# SparkFun_XBee_Arduino_Shield_Qwiic.net
KiCad netlist of a schematic drawn in EAGLE
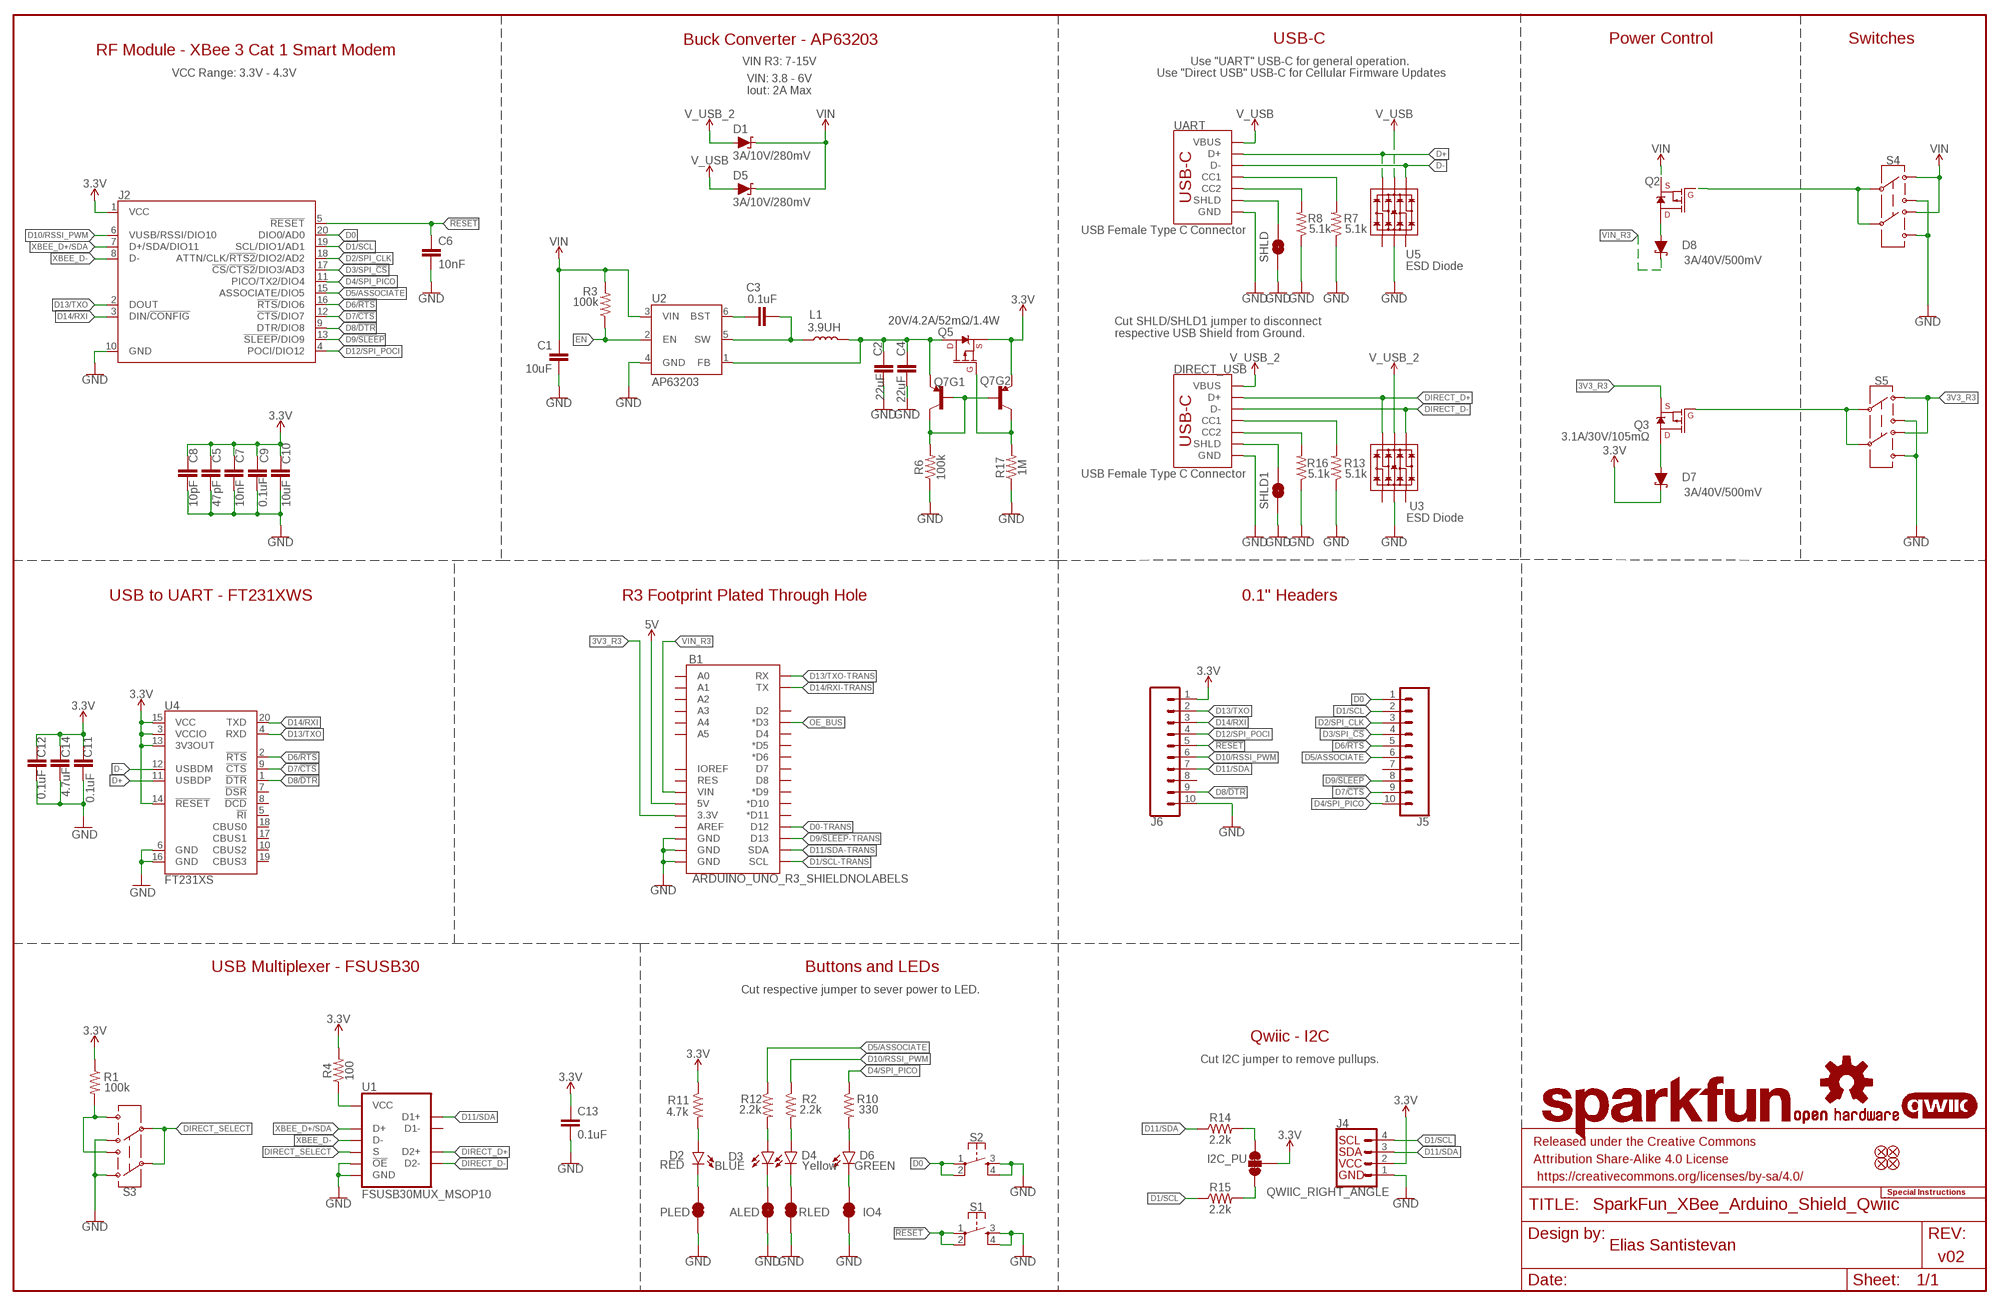
[diagram p0: schematic, sheet 1]

(export (version "E")
  (design (tool "Eeschema 10.0.6"))
  (components
    (comp (ref "ALED")
      (value "JUMPER-SMT_2_NC_TRACE_SILK")
      (footprint "eagle-import:SMT-JUMPER_2_NC_TRACE_SILK")
      (libsource (lib "eagle-import") (part "JUMPER-SMT_2_NC_TRACE_SILK"))
    )
    (comp (ref "B1")
      (value "ARDUINO_UNO_R3_SHIELDNOLABELS")
      (footprint "eagle-import:UNO_R3_SHIELD_NOLABELS")
      (libsource (lib "eagle-import") (part "ARDUINO_UNO_R3_SHIELDNOLABELS"))
    )
    (comp (ref "C1")
      (value "10uF")
      (footprint "eagle-import:1210")
      (libsource (lib "eagle-import") (part "10UF-1210-50V-20%"))
    )
    (comp (ref "C2")
      (value "22uF")
      (footprint "eagle-import:0603")
      (libsource (lib "eagle-import") (part "22UF-0603-6.3V-20%"))
    )
    (comp (ref "C3")
      (value "0.1uF")
      (footprint "eagle-import:0603")
      (libsource (lib "eagle-import") (part "0.1UF-0603-25V-5%"))
    )
    (comp (ref "C4")
      (value "22uF")
      (footprint "eagle-import:0603")
      (libsource (lib "eagle-import") (part "22UF-0603-6.3V-20%"))
    )
    (comp (ref "C5")
      (value "47pF")
      (footprint "eagle-import:0603")
      (libsource (lib "eagle-import") (part "47PF-0603-50V-5%"))
    )
    (comp (ref "C6")
      (value "10nF")
      (footprint "eagle-import:0603")
      (libsource (lib "eagle-import") (part "10NF-0603-50V-10%"))
    )
    (comp (ref "C7")
      (value "10nF")
      (footprint "eagle-import:0603")
      (libsource (lib "eagle-import") (part "10NF-0603-50V-10%"))
    )
    (comp (ref "C8")
      (value "10pF")
      (footprint "eagle-import:0603")
      (libsource (lib "eagle-import") (part "10PF-0603-50V-5%"))
    )
    (comp (ref "C9")
      (value "0.1uF")
      (footprint "eagle-import:0603")
      (libsource (lib "eagle-import") (part "0.1UF-0603-25V-(+80/-20%)"))
    )
    (comp (ref "C10")
      (value "10uF")
      (footprint "eagle-import:0603")
      (libsource (lib "eagle-import") (part "10UF-0603-6.3V-20%"))
    )
    (comp (ref "C11")
      (value "0.1uF")
      (footprint "eagle-import:0603")
      (libsource (lib "eagle-import") (part "0.1UF-0603-25V-(+80/-20%)"))
    )
    (comp (ref "C12")
      (value "0.1uF")
      (footprint "eagle-import:0603")
      (libsource (lib "eagle-import") (part "0.1UF-0603-25V-(+80/-20%)"))
    )
    (comp (ref "C13")
      (value "0.1uF")
      (footprint "eagle-import:0603")
      (libsource (lib "eagle-import") (part "0.1UF-0603-25V-(+80/-20%)"))
    )
    (comp (ref "C14")
      (value "4.7uF")
      (footprint "eagle-import:0603")
      (libsource (lib "eagle-import") (part "4.7UF-0603-6.3V-(10%)"))
    )
    (comp (ref "D1")
      (value "3A/10V/280mV")
      (footprint "eagle-import:SOD-323")
      (libsource (lib "eagle-import") (part "DIODE-SCHOTTKY-BAT60A"))
    )
    (comp (ref "D2")
      (value "RED")
      (footprint "eagle-import:LED-0603")
      (libsource (lib "eagle-import") (part "LED-RED_0603-KB"))
    )
    (comp (ref "D3")
      (value "BLUE")
      (footprint "eagle-import:LED-0603")
      (libsource (lib "eagle-import") (part "LED-BLUE0603"))
    )
    (comp (ref "D4")
      (value "Yellow")
      (footprint "eagle-import:LED-0603")
      (libsource (lib "eagle-import") (part "LED-YELLOW0603"))
    )
    (comp (ref "D5")
      (value "3A/10V/280mV")
      (footprint "eagle-import:SOD-323")
      (libsource (lib "eagle-import") (part "DIODE-SCHOTTKY-BAT60A"))
    )
    (comp (ref "D6")
      (value "GREEN")
      (footprint "eagle-import:LED-0603")
      (libsource (lib "eagle-import") (part "LED-GREEN0603"))
    )
    (comp (ref "D7")
      (value "3A/40V/500mV")
      (footprint "eagle-import:SMA-DIODE")
      (libsource (lib "eagle-import") (part "DIODE-SCHOTTKY-B340A"))
    )
    (comp (ref "D8")
      (value "3A/40V/500mV")
      (footprint "eagle-import:SMA-DIODE")
      (libsource (lib "eagle-import") (part "DIODE-SCHOTTKY-B340A"))
    )
    (comp (ref "DIRECT_USB")
      (value "USB Female Type C Connector")
      (footprint "eagle-import:USB-C-16P-4LAYER-ISOLATED")
      (libsource (lib "eagle-import") (part "USB_C_4-LAYER-ISOLATED"))
    )
    (comp (ref "FD1")
      (value "FIDUCIAL1X2")
      (footprint "eagle-import:FIDUCIAL-1X2")
      (libsource (lib "eagle-import") (part "FIDUCIAL1X2"))
    )
    (comp (ref "FD2")
      (value "FIDUCIAL1X2")
      (footprint "eagle-import:FIDUCIAL-1X2")
      (libsource (lib "eagle-import") (part "FIDUCIAL1X2"))
    )
    (comp (ref "FD3")
      (value "FIDUCIAL1X2")
      (footprint "eagle-import:FIDUCIAL-1X2")
      (libsource (lib "eagle-import") (part "FIDUCIAL1X2"))
    )
    (comp (ref "FD4")
      (value "FIDUCIAL1X2")
      (footprint "eagle-import:FIDUCIAL-1X2")
      (libsource (lib "eagle-import") (part "FIDUCIAL1X2"))
    )
    (comp (ref "FRAME1")
      (value "FRAME-LEDGER")
      (footprint "eagle-import:CREATIVE_COMMONS")
      (libsource (lib "eagle-import") (part "FRAME-LEDGER"))
    )
    (comp (ref "I2C_PU")
      (value "JUMPER-SMT_3_2-NC_TRACE_SILK")
      (footprint "eagle-import:SMT-JUMPER_3_2-NC_TRACE_SILK")
      (libsource (lib "eagle-import") (part "JUMPER-SMT_3_2-NC_TRACE_SILK"))
    )
    (comp (ref "IO4")
      (value "JUMPER-SMT_2_NC_TRACE_SILK")
      (footprint "eagle-import:SMT-JUMPER_2_NC_TRACE_SILK")
      (libsource (lib "eagle-import") (part "JUMPER-SMT_2_NC_TRACE_SILK"))
    )
    (comp (ref "J2")
      (value "XBEE_UPDATEXBEE_SMD")
      (footprint "eagle-import:XBEE3-SMD")
      (libsource (lib "eagle-import") (part "XBEE_UPDATEXBEE_SMD"))
    )
    (comp (ref "J4")
      (value "QWIIC_RIGHT_ANGLE")
      (footprint "eagle-import:JST04_1MM_RA")
      (libsource (lib "eagle-import") (part "QWIIC_CONNECTORJS-1MM"))
    )
    (comp (ref "J5")
      (value "CONN_10NO_SILK_PTH_FEMALE")
      (footprint "eagle-import:1X10_NO_SILK")
      (libsource (lib "eagle-import") (part "CONN_10NO_SILK_PTH_FEMALE"))
    )
    (comp (ref "J6")
      (value "CONN_10NO_SILK_PTH_FEMALE")
      (footprint "eagle-import:1X10_NO_SILK")
      (libsource (lib "eagle-import") (part "CONN_10NO_SILK_PTH_FEMALE"))
    )
    (comp (ref "L1")
      (value "3.9UH")
      (footprint "eagle-import:INDUCTOR_3.9UH")
      (libsource (lib "eagle-import") (part "3.9UH"))
    )
    (comp (ref "LOGO1")
      (value "SFE_LOGO_NAMEBLANK")
      (footprint "eagle-import:BLANK")
      (libsource (lib "eagle-import") (part "SFE_LOGO_NAMEBLANK"))
    )
    (comp (ref "LOGO2")
      (value "OSHW-LOGOS")
      (footprint "eagle-import:OSHW-LOGO-S")
      (libsource (lib "eagle-import") (part "OSHW-LOGOS"))
    )
    (comp (ref "LOGO3")
      (value "QWIIC_LOGO_4MM")
      (footprint "eagle-import:QWIIC_4MM")
      (libsource (lib "eagle-import") (part "QWIIC_LOGO_4MM"))
    )
    (comp (ref "LOGO4")
      (value "SPECIAL_INSTRUCTIONS-ORDERING")
      (footprint "eagle-import:ORDERING_INSTRUCTIONS")
      (libsource (lib "eagle-import") (part "SPECIAL_INSTRUCTIONS-ORDERING"))
    )
    (comp (ref "PLED")
      (value "JUMPER-SMT_2_NC_TRACE_SILK")
      (footprint "eagle-import:SMT-JUMPER_2_NC_TRACE_SILK")
      (libsource (lib "eagle-import") (part "JUMPER-SMT_2_NC_TRACE_SILK"))
    )
    (comp (ref "Q2")
      (value "20V/4.2A/52mΩ/1.4W")
      (footprint "eagle-import:SOT23-3")
      (libsource (lib "eagle-import") (part "MOSFET_PCH-DMG2305UX-7"))
    )
    (comp (ref "Q3")
      (value "3.1A/30V/105mΩ")
      (footprint "eagle-import:SOT23-3")
      (libsource (lib "eagle-import") (part "MOSFET_PCH-DMG2307L"))
    )
    (comp (ref "Q5")
      (value "20V/4.2A/52mΩ/1.4W")
      (footprint "eagle-import:SOT23-3")
      (libsource (lib "eagle-import") (part "MOSFET_PCH-DMG2305UX-7"))
    )
    (comp (ref "Q7")
      (value "TRANS_PNP_DUALSOT-363")
      (footprint "eagle-import:SOT363_PHILIPS")
      (libsource (lib "eagle-import") (part "TRANS_PNP_DUALSOT-363"))
    )
    (comp (ref "R1")
      (value "100k")
      (footprint "eagle-import:0603")
      (libsource (lib "eagle-import") (part "100KOHM-0603-1/10W-1%"))
    )
    (comp (ref "R2")
      (value "2.2k")
      (footprint "eagle-import:0603")
      (libsource (lib "eagle-import") (part "2.2KOHM-0603-1/10W-1%"))
    )
    (comp (ref "R3")
      (value "100k")
      (footprint "eagle-import:0603")
      (libsource (lib "eagle-import") (part "100KOHM-0603-1/10W-1%"))
    )
    (comp (ref "R4")
      (value "100")
      (footprint "eagle-import:0603")
      (libsource (lib "eagle-import") (part "100OHM-0603-1/10W-1%"))
    )
    (comp (ref "R6")
      (value "100k")
      (footprint "eagle-import:0603")
      (libsource (lib "eagle-import") (part "100KOHM-0603-1/10W-1%"))
    )
    (comp (ref "R7")
      (value "5.1k")
      (footprint "eagle-import:0603")
      (libsource (lib "eagle-import") (part "5.1KOHM5.1KOHM-0603-1/10W-1%"))
    )
    (comp (ref "R8")
      (value "5.1k")
      (footprint "eagle-import:0603")
      (libsource (lib "eagle-import") (part "5.1KOHM5.1KOHM-0603-1/10W-1%"))
    )
    (comp (ref "R10")
      (value "330")
      (footprint "eagle-import:0603")
      (libsource (lib "eagle-import") (part "330OHM-0603-1/10W-1%"))
    )
    (comp (ref "R11")
      (value "4.7k")
      (footprint "eagle-import:0603")
      (libsource (lib "eagle-import") (part "4.7KOHM-0603-1/10W-1%"))
    )
    (comp (ref "R12")
      (value "2.2k")
      (footprint "eagle-import:0603")
      (libsource (lib "eagle-import") (part "2.2KOHM-0603-1/10W-1%"))
    )
    (comp (ref "R13")
      (value "5.1k")
      (footprint "eagle-import:0603")
      (libsource (lib "eagle-import") (part "5.1KOHM5.1KOHM-0603-1/10W-1%"))
    )
    (comp (ref "R14")
      (value "2.2k")
      (footprint "eagle-import:0603")
      (libsource (lib "eagle-import") (part "2.2KOHM-0603-1/10W-1%"))
    )
    (comp (ref "R15")
      (value "2.2k")
      (footprint "eagle-import:0603")
      (libsource (lib "eagle-import") (part "2.2KOHM-0603-1/10W-1%"))
    )
    (comp (ref "R16")
      (value "5.1k")
      (footprint "eagle-import:0603")
      (libsource (lib "eagle-import") (part "5.1KOHM5.1KOHM-0603-1/10W-1%"))
    )
    (comp (ref "R17")
      (value "1M")
      (footprint "eagle-import:0603")
      (libsource (lib "eagle-import") (part "1MOHM-0603-1/4W-5%"))
    )
    (comp (ref "RLED")
      (value "JUMPER-SMT_2_NC_TRACE_SILK")
      (footprint "eagle-import:SMT-JUMPER_2_NC_TRACE_SILK")
      (libsource (lib "eagle-import") (part "JUMPER-SMT_2_NC_TRACE_SILK"))
    )
    (comp (ref "S1")
      (value "MOMENTARY-SWITCH-SPST-2-SMD-5.2MM-TALL")
      (footprint "eagle-import:TACTILE_SWITCH_SMD_5.2MM")
      (libsource (lib "eagle-import") (part "MOMENTARY-SWITCH-SPST-2-SMD-5.2MM-TALL"))
    )
    (comp (ref "S2")
      (value "MOMENTARY-SWITCH-SPST-2-SMD-5.2MM-TALL")
      (footprint "eagle-import:TACTILE_SWITCH_SMD_5.2MM")
      (libsource (lib "eagle-import") (part "MOMENTARY-SWITCH-SPST-2-SMD-5.2MM-TALL"))
    )
    (comp (ref "S3")
      (value "SWITCH-DPDT-SMD-AYZ0202")
      (footprint "eagle-import:SWITCH_DPDT_SMD_AYZ0202")
      (libsource (lib "eagle-import") (part "SWITCH-DPDT-SMD-AYZ0202"))
    )
    (comp (ref "S4")
      (value "SWITCH-DPDT-SMD-AYZ0202")
      (footprint "eagle-import:SWITCH_DPDT_SMD_AYZ0202")
      (libsource (lib "eagle-import") (part "SWITCH-DPDT-SMD-AYZ0202"))
    )
    (comp (ref "S5")
      (value "SWITCH-DPDT-SMD-AYZ0202")
      (footprint "eagle-import:SWITCH_DPDT_SMD_AYZ0202")
      (libsource (lib "eagle-import") (part "SWITCH-DPDT-SMD-AYZ0202"))
    )
    (comp (ref "SHLD")
      (value "JUMPER-SMT_2_NC_TRACE_SILK")
      (footprint "eagle-import:SMT-JUMPER_2_NC_TRACE_SILK")
      (libsource (lib "eagle-import") (part "JUMPER-SMT_2_NC_TRACE_SILK"))
    )
    (comp (ref "SHLD1")
      (value "JUMPER-SMT_2_NC_TRACE_SILK")
      (footprint "eagle-import:SMT-JUMPER_2_NC_TRACE_SILK")
      (libsource (lib "eagle-import") (part "JUMPER-SMT_2_NC_TRACE_SILK"))
    )
    (comp (ref "U1")
      (value "FSUSB30MUX_MSOP10")
      (footprint "eagle-import:MSOP10")
      (libsource (lib "eagle-import") (part "FSUSB30MUX_MSOP10"))
    )
    (comp (ref "U2")
      (value "AP63203")
      (footprint "eagle-import:SOT23-6")
      (libsource (lib "eagle-import") (part "AP63203"))
    )
    (comp (ref "U3")
      (value "ESD Diode")
      (footprint "eagle-import:SOT-23-6")
      (libsource (lib "eagle-import") (part "TVS_DIODE_ARRAY_DT1042-04SO-7"))
    )
    (comp (ref "U4")
      (value "FT231XS")
      (footprint "eagle-import:SSOP20_L")
      (libsource (lib "eagle-import") (part "FT231XS"))
    )
    (comp (ref "U5")
      (value "ESD Diode")
      (footprint "eagle-import:SOT-23-6")
      (libsource (lib "eagle-import") (part "TVS_DIODE_ARRAY_DT1042-04SO-7"))
    )
    (comp (ref "UART")
      (value "USB Female Type C Connector")
      (footprint "eagle-import:USB-C-16P-4LAYER-ISOLATED")
      (libsource (lib "eagle-import") (part "USB_C_4-LAYER-ISOLATED"))
    )
  )
  (nets
    (net (code "1") (name "/D3{slash}SPI_~{CS}") (class "Default")
      (node (ref "J2") (pin "17") (pinfunction "~{CS}/~{CTS2}/DIO3/AD3_17") (pintype "bidirectional"))
      (node (ref "J5") (pin "4") (pinfunction "4_4") (pintype "passive"))
    )
    (net (code "2") (name "/D6{slash}~{RTS}") (class "Default")
      (node (ref "J2") (pin "16") (pinfunction "~{RTS}/DIO6_16") (pintype "input"))
      (node (ref "J5") (pin "5") (pinfunction "5_5") (pintype "passive"))
      (node (ref "U4") (pin "2") (pinfunction "~{RTS}_2") (pintype "bidirectional"))
    )
    (net (code "3") (name "/D7{slash}~{CTS}") (class "Default")
      (node (ref "J2") (pin "12") (pinfunction "~{CTS}/DIO7_12") (pintype "output"))
      (node (ref "J5") (pin "9") (pinfunction "9_9") (pintype "passive"))
      (node (ref "U4") (pin "9") (pinfunction "~{CTS}_9") (pintype "bidirectional"))
    )
    (net (code "4") (name "/D8{slash}~{DTR}") (class "Default")
      (node (ref "J2") (pin "9") (pinfunction "DTR/DIO8_9") (pintype "bidirectional"))
      (node (ref "J6") (pin "9") (pinfunction "9_9") (pintype "passive"))
      (node (ref "U4") (pin "1") (pinfunction "~{DTR}_1") (pintype "bidirectional"))
    )
    (net (code "5") (name "/D9{slash}~{SLEEP}") (class "Default")
      (node (ref "J2") (pin "13") (pinfunction "~{SLEEP}/DIO9_13") (pintype "bidirectional"))
      (node (ref "J5") (pin "8") (pinfunction "8_8") (pintype "passive"))
    )
    (net (code "6") (name "/D9{slash}~{SLEEP}-TRANS") (class "Default")
      (node (ref "B1") (pin "D13") (pinfunction "D13_D13") (pintype "bidirectional"))
    )
    (net (code "7") (name "/~{RESET}") (class "Default")
      (node (ref "C6") (pin "1") (pinfunction "1_1") (pintype "passive"))
      (node (ref "J2") (pin "5") (pinfunction "~{RESET}_5") (pintype "input"))
      (node (ref "J6") (pin "5") (pinfunction "5_5") (pintype "passive"))
      (node (ref "S1") (pin "1") (pinfunction "1_1") (pintype "passive"))
      (node (ref "S1") (pin "2") (pinfunction "2_2") (pintype "passive"))
    )
    (net (code "8") (name "3.3V") (class "Default")
      (node (ref "C10") (pin "1") (pinfunction "1_1") (pintype "passive"))
      (node (ref "C11") (pin "1") (pinfunction "1_1") (pintype "passive"))
      (node (ref "C12") (pin "1") (pinfunction "1_1") (pintype "passive"))
      (node (ref "C13") (pin "1") (pinfunction "1_1") (pintype "passive"))
      (node (ref "C14") (pin "1") (pinfunction "1_1") (pintype "passive"))
      (node (ref "C5") (pin "1") (pinfunction "1_1") (pintype "passive"))
      (node (ref "C7") (pin "1") (pinfunction "1_1") (pintype "passive"))
      (node (ref "C8") (pin "1") (pinfunction "1_1") (pintype "passive"))
      (node (ref "C9") (pin "1") (pinfunction "1_1") (pintype "passive"))
      (node (ref "D7") (pin "C") (pinfunction "C_C") (pintype "passive"))
      (node (ref "I2C_PU") (pin "2") (pinfunction "2_2") (pintype "passive"))
      (node (ref "J2") (pin "1") (pinfunction "VCC_1") (pintype "power_in"))
      (node (ref "J4") (pin "2") (pinfunction "2_2") (pintype "power_in"))
      (node (ref "J6") (pin "1") (pinfunction "1_1") (pintype "passive"))
      (node (ref "Q5") (pin "2") (pinfunction "S_2") (pintype "bidirectional"))
      (node (ref "Q7") (pin "4") (pinfunction "E_4") (pintype "passive"))
      (node (ref "R1") (pin "1") (pinfunction "1_1") (pintype "passive"))
      (node (ref "R11") (pin "1") (pinfunction "1_1") (pintype "passive"))
      (node (ref "R4") (pin "2") (pinfunction "2_2") (pintype "passive"))
      (node (ref "U4") (pin "13") (pinfunction "3V3OUT_13") (pintype "bidirectional"))
      (node (ref "U4") (pin "14") (pinfunction "~{RESET}_14") (pintype "bidirectional"))
      (node (ref "U4") (pin "15") (pinfunction "VCC_15") (pintype "bidirectional"))
      (node (ref "U4") (pin "3") (pinfunction "VCCIO_3") (pintype "bidirectional"))
    )
    (net (code "9") (name "3V3_R3") (class "Default")
      (node (ref "B1") (pin "3.3V") (pinfunction "3.3V_3.3V") (pintype "bidirectional"))
      (node (ref "Q3") (pin "2") (pinfunction "S_2") (pintype "bidirectional"))
      (node (ref "S5") (pin "3") (pinfunction "3_3") (pintype "bidirectional"))
      (node (ref "S5") (pin "6") (pinfunction "6_6") (pintype "bidirectional"))
    )
    (net (code "10") (name "5V") (class "Default")
      (node (ref "B1") (pin "5V") (pinfunction "5V_5V") (pintype "bidirectional"))
    )
    (net (code "11") (name "D+") (class "Default")
      (node (ref "U4") (pin "11") (pinfunction "USBDP_11") (pintype "bidirectional"))
      (node (ref "U5") (pin "6") (pinfunction "IO4_6") (pintype "bidirectional"))
      (node (ref "UART") (pin "A6") (pinfunction "D+_A6") (pintype "bidirectional"))
      (node (ref "UART") (pin "B6") (pinfunction "D+_B6") (pintype "bidirectional"))
    )
    (net (code "12") (name "D-") (class "Default")
      (node (ref "U4") (pin "12") (pinfunction "USBDM_12") (pintype "bidirectional"))
      (node (ref "U5") (pin "4") (pinfunction "IO3_4") (pintype "bidirectional"))
      (node (ref "UART") (pin "A7") (pinfunction "D-_A7") (pintype "bidirectional"))
      (node (ref "UART") (pin "B7") (pinfunction "D-_B7") (pintype "bidirectional"))
    )
    (net (code "13") (name "D0") (class "Default")
      (node (ref "J2") (pin "20") (pinfunction "DIO0/AD0_20") (pintype "bidirectional"))
      (node (ref "J5") (pin "1") (pinfunction "1_1") (pintype "passive"))
      (node (ref "S2") (pin "1") (pinfunction "1_1") (pintype "passive"))
      (node (ref "S2") (pin "2") (pinfunction "2_2") (pintype "passive"))
    )
    (net (code "14") (name "D0-TRANS") (class "Default")
      (node (ref "B1") (pin "D12") (pinfunction "D12_D12") (pintype "bidirectional"))
    )
    (net (code "15") (name "D1{slash}SCL") (class "Default")
      (node (ref "J2") (pin "19") (pinfunction "SCL/DIO1/AD1_19") (pintype "bidirectional"))
      (node (ref "J4") (pin "4") (pinfunction "4_4") (pintype "passive"))
      (node (ref "J5") (pin "2") (pinfunction "2_2") (pintype "passive"))
      (node (ref "R15") (pin "1") (pinfunction "1_1") (pintype "passive"))
    )
    (net (code "16") (name "D1{slash}SCL-TRANS") (class "Default")
      (node (ref "B1") (pin "SCL") (pinfunction "SCL_SCL") (pintype "bidirectional"))
    )
    (net (code "17") (name "D2{slash}SPI_CLK") (class "Default")
      (node (ref "J2") (pin "18") (pinfunction "ATTN/CLK/~{RTS2}/DIO2/AD2_18") (pintype "bidirectional"))
      (node (ref "J5") (pin "3") (pinfunction "3_3") (pintype "passive"))
    )
    (net (code "18") (name "D4{slash}SPI_PICO") (class "Default")
      (node (ref "J2") (pin "11") (pinfunction "PICO/TX2/DIO4_11") (pintype "bidirectional"))
      (node (ref "J5") (pin "10") (pinfunction "10_10") (pintype "passive"))
      (node (ref "R10") (pin "1") (pinfunction "1_1") (pintype "passive"))
    )
    (net (code "19") (name "D5{slash}ASSOCIATE") (class "Default")
      (node (ref "J2") (pin "15") (pinfunction "ASSOCIATE/DIO5_15") (pintype "bidirectional"))
      (node (ref "J5") (pin "6") (pinfunction "6_6") (pintype "passive"))
      (node (ref "R12") (pin "1") (pinfunction "1_1") (pintype "passive"))
    )
    (net (code "20") (name "D10{slash}RSSI_PWM") (class "Default")
      (node (ref "J2") (pin "6") (pinfunction "VUSB/RSSI/DIO10_6") (pintype "bidirectional"))
      (node (ref "J6") (pin "6") (pinfunction "6_6") (pintype "passive"))
      (node (ref "R2") (pin "1") (pinfunction "1_1") (pintype "passive"))
    )
    (net (code "21") (name "D11{slash}SDA") (class "Default")
      (node (ref "J4") (pin "3") (pinfunction "3_3") (pintype "passive"))
      (node (ref "J6") (pin "7") (pinfunction "7_7") (pintype "passive"))
      (node (ref "R14") (pin "1") (pinfunction "1_1") (pintype "passive"))
      (node (ref "U1") (pin "2") (pinfunction "D1+_2") (pintype "bidirectional"))
    )
    (net (code "22") (name "D11{slash}SDA-TRANS") (class "Default")
      (node (ref "B1") (pin "SDA") (pinfunction "SDA_SDA") (pintype "bidirectional"))
    )
    (net (code "23") (name "D12{slash}SPI_POCI") (class "Default")
      (node (ref "J2") (pin "4") (pinfunction "POCI/DIO12_4") (pintype "bidirectional"))
      (node (ref "J6") (pin "4") (pinfunction "4_4") (pintype "passive"))
    )
    (net (code "24") (name "D13{slash}TXO") (class "Default")
      (node (ref "J2") (pin "2") (pinfunction "DOUT_2") (pintype "output"))
      (node (ref "J6") (pin "2") (pinfunction "2_2") (pintype "passive"))
      (node (ref "U4") (pin "4") (pinfunction "RXD_4") (pintype "bidirectional"))
    )
    (net (code "25") (name "D13{slash}TXO-TRANS") (class "Default")
      (node (ref "B1") (pin "RX") (pinfunction "RX_RX") (pintype "bidirectional"))
    )
    (net (code "26") (name "D14{slash}RXI") (class "Default")
      (node (ref "J2") (pin "3") (pinfunction "DIN/~{CONFIG}_3") (pintype "input"))
      (node (ref "J6") (pin "3") (pinfunction "3_3") (pintype "passive"))
      (node (ref "U4") (pin "20") (pinfunction "TXD_20") (pintype "bidirectional"))
    )
    (net (code "27") (name "D14{slash}RXI-TRANS") (class "Default")
      (node (ref "B1") (pin "TX") (pinfunction "TX_TX") (pintype "bidirectional"))
    )
    (net (code "28") (name "DIRECT_D+") (class "Default")
      (node (ref "DIRECT_USB") (pin "A6") (pinfunction "D+_A6") (pintype "bidirectional"))
      (node (ref "DIRECT_USB") (pin "B6") (pinfunction "D+_B6") (pintype "bidirectional"))
      (node (ref "U1") (pin "3") (pinfunction "D2+_3") (pintype "bidirectional"))
      (node (ref "U3") (pin "6") (pinfunction "IO4_6") (pintype "bidirectional"))
    )
    (net (code "29") (name "DIRECT_D-") (class "Default")
      (node (ref "DIRECT_USB") (pin "A7") (pinfunction "D-_A7") (pintype "bidirectional"))
      (node (ref "DIRECT_USB") (pin "B7") (pinfunction "D-_B7") (pintype "bidirectional"))
      (node (ref "U1") (pin "7") (pinfunction "D2-_7") (pintype "bidirectional"))
      (node (ref "U3") (pin "4") (pinfunction "IO3_4") (pintype "bidirectional"))
    )
    (net (code "30") (name "DIRECT_SELECT") (class "Default")
      (node (ref "S3") (pin "2") (pinfunction "2_2") (pintype "bidirectional"))
      (node (ref "S3") (pin "5") (pinfunction "5_5") (pintype "bidirectional"))
      (node (ref "U1") (pin "1") (pinfunction "S_1") (pintype "bidirectional"))
    )
    (net (code "31") (name "EN") (class "Default")
      (node (ref "R3") (pin "1") (pinfunction "1_1") (pintype "passive"))
      (node (ref "U2") (pin "2") (pinfunction "EN_2") (pintype "bidirectional"))
    )
    (net (code "32") (name "GND") (class "Default")
      (node (ref "ALED") (pin "1") (pinfunction "1_1") (pintype "passive"))
      (node (ref "B1") (pin "GND@0") (pinfunction "GND_GND@0") (pintype "bidirectional"))
      (node (ref "B1") (pin "GND@1") (pinfunction "GND_GND@1") (pintype "bidirectional"))
      (node (ref "B1") (pin "GND@2") (pinfunction "GND_GND@2") (pintype "bidirectional"))
      (node (ref "C1") (pin "2") (pinfunction "2_2") (pintype "passive"))
      (node (ref "C10") (pin "2") (pinfunction "2_2") (pintype "passive"))
      (node (ref "C11") (pin "2") (pinfunction "2_2") (pintype "passive"))
      (node (ref "C12") (pin "2") (pinfunction "2_2") (pintype "passive"))
      (node (ref "C13") (pin "2") (pinfunction "2_2") (pintype "passive"))
      (node (ref "C14") (pin "2") (pinfunction "2_2") (pintype "passive"))
      (node (ref "C2") (pin "2") (pinfunction "2_2") (pintype "passive"))
      (node (ref "C4") (pin "2") (pinfunction "2_2") (pintype "passive"))
      (node (ref "C5") (pin "2") (pinfunction "2_2") (pintype "passive"))
      (node (ref "C6") (pin "2") (pinfunction "2_2") (pintype "passive"))
      (node (ref "C7") (pin "2") (pinfunction "2_2") (pintype "passive"))
      (node (ref "C8") (pin "2") (pinfunction "2_2") (pintype "passive"))
      (node (ref "C9") (pin "2") (pinfunction "2_2") (pintype "passive"))
      (node (ref "DIRECT_USB") (pin "GND") (pinfunction "GND_GND") (pintype "bidirectional"))
      (node (ref "DIRECT_USB") (pin "GND2") (pinfunction "GND_GND2") (pintype "bidirectional"))
      (node (ref "IO4") (pin "1") (pinfunction "1_1") (pintype "passive"))
      (node (ref "J2") (pin "10") (pinfunction "GND_10") (pintype "power_in"))
      (node (ref "J4") (pin "1") (pinfunction "1_1") (pintype "power_in"))
      (node (ref "J6") (pin "10") (pinfunction "10_10") (pintype "passive"))
      (node (ref "PLED") (pin "1") (pinfunction "1_1") (pintype "passive"))
      (node (ref "R13") (pin "1") (pinfunction "1_1") (pintype "passive"))
      (node (ref "R16") (pin "1") (pinfunction "1_1") (pintype "passive"))
      (node (ref "R17") (pin "1") (pinfunction "1_1") (pintype "passive"))
      (node (ref "R6") (pin "1") (pinfunction "1_1") (pintype "passive"))
      (node (ref "R7") (pin "1") (pinfunction "1_1") (pintype "passive"))
      (node (ref "R8") (pin "1") (pinfunction "1_1") (pintype "passive"))
      (node (ref "RLED") (pin "1") (pinfunction "1_1") (pintype "passive"))
      (node (ref "S1") (pin "3") (pinfunction "3_3") (pintype "passive"))
      (node (ref "S1") (pin "4") (pinfunction "4_4") (pintype "passive"))
      (node (ref "S2") (pin "3") (pinfunction "3_3") (pintype "passive"))
      (node (ref "S2") (pin "4") (pinfunction "4_4") (pintype "passive"))
      (node (ref "S3") (pin "3") (pinfunction "3_3") (pintype "bidirectional"))
      (node (ref "S3") (pin "6") (pinfunction "6_6") (pintype "bidirectional"))
      (node (ref "S4") (pin "1") (pinfunction "1_1") (pintype "bidirectional"))
      (node (ref "S4") (pin "4") (pinfunction "4_4") (pintype "bidirectional"))
      (node (ref "S5") (pin "1") (pinfunction "1_1") (pintype "bidirectional"))
      (node (ref "S5") (pin "4") (pinfunction "4_4") (pintype "bidirectional"))
      (node (ref "SHLD") (pin "1") (pinfunction "1_1") (pintype "passive"))
      (node (ref "SHLD1") (pin "1") (pinfunction "1_1") (pintype "passive"))
      (node (ref "U1") (pin "5") (pinfunction "GND_5") (pintype "bidirectional"))
      (node (ref "U1") (pin "9") (pinfunction "~{OE}_9") (pintype "bidirectional"))
      (node (ref "U2") (pin "4") (pinfunction "GND_4") (pintype "bidirectional"))
      (node (ref "U3") (pin "2") (pinfunction "VSS_2") (pintype "bidirectional"))
      (node (ref "U4") (pin "16") (pinfunction "GND_16") (pintype "bidirectional"))
      (node (ref "U4") (pin "6") (pinfunction "GND_6") (pintype "bidirectional"))
      (node (ref "U5") (pin "2") (pinfunction "VSS_2") (pintype "bidirectional"))
      (node (ref "UART") (pin "GND") (pinfunction "GND_GND") (pintype "bidirectional"))
      (node (ref "UART") (pin "GND2") (pinfunction "GND_GND2") (pintype "bidirectional"))
    )
    (net (code "33") (name "Net-(ALED-Pad2)") (class "Default")
      (node (ref "ALED") (pin "2") (pinfunction "2_2") (pintype "passive"))
      (node (ref "D3") (pin "C") (pinfunction "C_C") (pintype "passive"))
    )
    (net (code "34") (name "Net-(D2-PadA)") (class "Default")
      (node (ref "D2") (pin "A") (pinfunction "A_A") (pintype "passive"))
      (node (ref "R11") (pin "2") (pinfunction "2_2") (pintype "passive"))
    )
    (net (code "35") (name "Net-(D2-PadC)") (class "Default")
      (node (ref "D2") (pin "C") (pinfunction "C_C") (pintype "passive"))
      (node (ref "PLED") (pin "2") (pinfunction "2_2") (pintype "passive"))
    )
    (net (code "36") (name "Net-(D3-PadA)") (class "Default")
      (node (ref "D3") (pin "A") (pinfunction "A_A") (pintype "passive"))
      (node (ref "R12") (pin "2") (pinfunction "2_2") (pintype "passive"))
    )
    (net (code "37") (name "Net-(D4-PadA)") (class "Default")
      (node (ref "D4") (pin "A") (pinfunction "A_A") (pintype "passive"))
      (node (ref "R2") (pin "2") (pinfunction "2_2") (pintype "passive"))
    )
    (net (code "38") (name "Net-(D4-PadC)") (class "Default")
      (node (ref "D4") (pin "C") (pinfunction "C_C") (pintype "passive"))
      (node (ref "RLED") (pin "2") (pinfunction "2_2") (pintype "passive"))
    )
    (net (code "39") (name "Net-(D6-PadA)") (class "Default")
      (node (ref "D6") (pin "A") (pinfunction "A_A") (pintype "passive"))
      (node (ref "R10") (pin "2") (pinfunction "2_2") (pintype "passive"))
    )
    (net (code "40") (name "Net-(D6-PadC)") (class "Default")
      (node (ref "D6") (pin "C") (pinfunction "C_C") (pintype "passive"))
      (node (ref "IO4") (pin "2") (pinfunction "2_2") (pintype "passive"))
    )
    (net (code "41") (name "Net-(DIRECT_USB-CC1)") (class "Default")
      (node (ref "DIRECT_USB") (pin "A5") (pinfunction "CC1_A5") (pintype "bidirectional"))
      (node (ref "R13") (pin "2") (pinfunction "2_2") (pintype "passive"))
    )
    (net (code "42") (name "Net-(DIRECT_USB-CC2)") (class "Default")
      (node (ref "DIRECT_USB") (pin "B5") (pinfunction "CC2_B5") (pintype "bidirectional"))
      (node (ref "R16") (pin "2") (pinfunction "2_2") (pintype "passive"))
    )
    (net (code "43") (name "Net-(DIRECT_USB-SHLD-PadSHLD1)") (class "Default")
      (node (ref "DIRECT_USB") (pin "SHLD1") (pinfunction "SHLD_SHLD1") (pintype "bidirectional"))
      (node (ref "DIRECT_USB") (pin "SHLD2") (pinfunction "SHLD_SHLD2") (pintype "bidirectional"))
      (node (ref "DIRECT_USB") (pin "SHLD3") (pinfunction "SHLD_SHLD3") (pintype "bidirectional"))
      (node (ref "DIRECT_USB") (pin "SHLD4") (pinfunction "SHLD_SHLD4") (pintype "bidirectional"))
      (node (ref "DIRECT_USB") (pin "SHLD5") (pinfunction "SHLD_SHLD5") (pintype "bidirectional"))
      (node (ref "DIRECT_USB") (pin "SHLD6") (pinfunction "SHLD_SHLD6") (pintype "bidirectional"))
      (node (ref "DIRECT_USB") (pin "SHLD7") (pinfunction "SHLD_SHLD7") (pintype "bidirectional"))
      (node (ref "DIRECT_USB") (pin "SHLD8") (pinfunction "SHLD_SHLD8") (pintype "bidirectional"))
      (node (ref "SHLD1") (pin "2") (pinfunction "2_2") (pintype "passive"))
    )
    (net (code "44") (name "Net-(I2C_PU-Pad1)") (class "Default")
      (node (ref "I2C_PU") (pin "1") (pinfunction "1_1") (pintype "passive"))
      (node (ref "R15") (pin "2") (pinfunction "2_2") (pintype "passive"))
    )
    (net (code "45") (name "Net-(I2C_PU-Pad3)") (class "Default")
      (node (ref "I2C_PU") (pin "3") (pinfunction "3_3") (pintype "passive"))
      (node (ref "R14") (pin "2") (pinfunction "2_2") (pintype "passive"))
    )
    (net (code "46") (name "Net-(L1-1)") (class "Default")
      (node (ref "C3") (pin "2") (pinfunction "2_2") (pintype "passive"))
      (node (ref "L1") (pin "P$1") (pinfunction "1_P$1") (pintype "passive"))
      (node (ref "U2") (pin "5") (pinfunction "SW_5") (pintype "bidirectional"))
    )
    (net (code "47") (name "Net-(L1-2)") (class "Default")
      (node (ref "C2") (pin "1") (pinfunction "1_1") (pintype "passive"))
      (node (ref "C4") (pin "1") (pinfunction "1_1") (pintype "passive"))
      (node (ref "L1") (pin "P$2") (pinfunction "2_P$2") (pintype "passive"))
      (node (ref "Q5") (pin "3") (pinfunction "D_3") (pintype "bidirectional"))
      (node (ref "Q7") (pin "1") (pinfunction "E_1") (pintype "passive"))
      (node (ref "U2") (pin "1") (pinfunction "FB_1") (pintype "bidirectional"))
    )
    (net (code "48") (name "Net-(Q2-D)") (class "Default")
      (node (ref "D8") (pin "A") (pinfunction "A_A") (pintype "passive"))
      (node (ref "Q2") (pin "3") (pinfunction "D_3") (pintype "bidirectional"))
    )
    (net (code "49") (name "Net-(Q2-G)") (class "Default")
      (node (ref "Q2") (pin "1") (pinfunction "G_1") (pintype "bidirectional"))
      (node (ref "S4") (pin "2") (pinfunction "2_2") (pintype "bidirectional"))
      (node (ref "S4") (pin "5") (pinfunction "5_5") (pintype "bidirectional"))
    )
    (net (code "50") (name "Net-(Q3-D)") (class "Default")
      (node (ref "D7") (pin "A") (pinfunction "A_A") (pintype "passive"))
      (node (ref "Q3") (pin "3") (pinfunction "D_3") (pintype "bidirectional"))
    )
    (net (code "51") (name "Net-(Q3-G)") (class "Default")
      (node (ref "Q3") (pin "1") (pinfunction "G_1") (pintype "bidirectional"))
      (node (ref "S5") (pin "2") (pinfunction "2_2") (pintype "bidirectional"))
      (node (ref "S5") (pin "5") (pinfunction "5_5") (pintype "bidirectional"))
    )
    (net (code "52") (name "Net-(Q5-G)") (class "Default")
      (node (ref "Q5") (pin "1") (pinfunction "G_1") (pintype "bidirectional"))
      (node (ref "Q7") (pin "3") (pinfunction "C_3") (pintype "passive"))
      (node (ref "R17") (pin "2") (pinfunction "2_2") (pintype "passive"))
    )
    (net (code "53") (name "Net-(Q7A-B)") (class "Default")
      (node (ref "Q7") (pin "2") (pinfunction "B_2") (pintype "passive"))
      (node (ref "Q7") (pin "5") (pinfunction "B_5") (pintype "passive"))
      (node (ref "Q7") (pin "6") (pinfunction "C_6") (pintype "passive"))
      (node (ref "R6") (pin "2") (pinfunction "2_2") (pintype "passive"))
    )
    (net (code "54") (name "Net-(R1-Pad2)") (class "Default")
      (node (ref "R1") (pin "2") (pinfunction "2_2") (pintype "passive"))
      (node (ref "S3") (pin "1") (pinfunction "1_1") (pintype "bidirectional"))
      (node (ref "S3") (pin "4") (pinfunction "4_4") (pintype "bidirectional"))
    )
    (net (code "55") (name "Net-(SHLD-Pad2)") (class "Default")
      (node (ref "SHLD") (pin "2") (pinfunction "2_2") (pintype "passive"))
      (node (ref "UART") (pin "SHLD1") (pinfunction "SHLD_SHLD1") (pintype "bidirectional"))
      (node (ref "UART") (pin "SHLD2") (pinfunction "SHLD_SHLD2") (pintype "bidirectional"))
      (node (ref "UART") (pin "SHLD3") (pinfunction "SHLD_SHLD3") (pintype "bidirectional"))
      (node (ref "UART") (pin "SHLD4") (pinfunction "SHLD_SHLD4") (pintype "bidirectional"))
      (node (ref "UART") (pin "SHLD5") (pinfunction "SHLD_SHLD5") (pintype "bidirectional"))
      (node (ref "UART") (pin "SHLD6") (pinfunction "SHLD_SHLD6") (pintype "bidirectional"))
      (node (ref "UART") (pin "SHLD7") (pinfunction "SHLD_SHLD7") (pintype "bidirectional"))
      (node (ref "UART") (pin "SHLD8") (pinfunction "SHLD_SHLD8") (pintype "bidirectional"))
    )
    (net (code "56") (name "Net-(U1-VCC)") (class "Default")
      (node (ref "R4") (pin "1") (pinfunction "1_1") (pintype "passive"))
      (node (ref "U1") (pin "10") (pinfunction "VCC_10") (pintype "bidirectional"))
    )
    (net (code "57") (name "Net-(U2-BST)") (class "Default")
      (node (ref "C3") (pin "1") (pinfunction "1_1") (pintype "passive"))
      (node (ref "U2") (pin "6") (pinfunction "BST_6") (pintype "bidirectional"))
    )
    (net (code "58") (name "Net-(UART-CC1)") (class "Default")
      (node (ref "R7") (pin "2") (pinfunction "2_2") (pintype "passive"))
      (node (ref "UART") (pin "A5") (pinfunction "CC1_A5") (pintype "bidirectional"))
    )
    (net (code "59") (name "Net-(UART-CC2)") (class "Default")
      (node (ref "R8") (pin "2") (pinfunction "2_2") (pintype "passive"))
      (node (ref "UART") (pin "B5") (pinfunction "CC2_B5") (pintype "bidirectional"))
    )
    (net (code "60") (name "OE_BUS") (class "Default")
      (node (ref "B1") (pin "D3") (pinfunction "*D3_D3") (pintype "bidirectional"))
    )
    (net (code "61") (name "VIN") (class "Default")
      (node (ref "C1") (pin "1") (pinfunction "1_1") (pintype "passive"))
      (node (ref "D1") (pin "C") (pinfunction "C_C") (pintype "passive"))
      (node (ref "D5") (pin "C") (pinfunction "C_C") (pintype "passive"))
      (node (ref "Q2") (pin "2") (pinfunction "S_2") (pintype "bidirectional"))
      (node (ref "R3") (pin "2") (pinfunction "2_2") (pintype "passive"))
      (node (ref "S4") (pin "3") (pinfunction "3_3") (pintype "bidirectional"))
      (node (ref "S4") (pin "6") (pinfunction "6_6") (pintype "bidirectional"))
      (node (ref "U2") (pin "3") (pinfunction "VIN_3") (pintype "bidirectional"))
    )
    (net (code "62") (name "VIN_R3") (class "Default")
      (node (ref "B1") (pin "VIN") (pinfunction "VIN_VIN") (pintype "bidirectional"))
      (node (ref "D8") (pin "C") (pinfunction "C_C") (pintype "passive"))
    )
    (net (code "63") (name "V_USB") (class "Default")
      (node (ref "D5") (pin "A") (pinfunction "A_A") (pintype "passive"))
      (node (ref "U5") (pin "5") (pinfunction "VCC_5") (pintype "bidirectional"))
      (node (ref "UART") (pin "VBUS1") (pinfunction "VBUS_VBUS1") (pintype "bidirectional"))
      (node (ref "UART") (pin "VBUS2") (pinfunction "VBUS_VBUS2") (pintype "bidirectional"))
    )
    (net (code "64") (name "V_USB_2") (class "Default")
      (node (ref "D1") (pin "A") (pinfunction "A_A") (pintype "passive"))
      (node (ref "DIRECT_USB") (pin "VBUS1") (pinfunction "VBUS_VBUS1") (pintype "bidirectional"))
      (node (ref "DIRECT_USB") (pin "VBUS2") (pinfunction "VBUS_VBUS2") (pintype "bidirectional"))
      (node (ref "U3") (pin "5") (pinfunction "VCC_5") (pintype "bidirectional"))
    )
    (net (code "65") (name "XBEE_D+{slash}SDA") (class "Default")
      (node (ref "J2") (pin "7") (pinfunction "D+/SDA/DIO11_7") (pintype "bidirectional"))
      (node (ref "U1") (pin "4") (pinfunction "D+_4") (pintype "bidirectional"))
    )
    (net (code "66") (name "XBEE_D-") (class "Default")
      (node (ref "J2") (pin "8") (pinfunction "D-_8") (pintype "bidirectional"))
      (node (ref "U1") (pin "6") (pinfunction "D-_6") (pintype "bidirectional"))
    )
    (net (code "67") (name "unconnected-(B1-*D5-PadD5)") (class "Default")
      (node (ref "B1") (pin "D5") (pinfunction "*D5_D5") (pintype "bidirectional"))
    )
    (net (code "68") (name "unconnected-(B1-*D6-PadD6)") (class "Default")
      (node (ref "B1") (pin "D6") (pinfunction "*D6_D6") (pintype "bidirectional"))
    )
    (net (code "69") (name "unconnected-(B1-*D9-PadD9)") (class "Default")
      (node (ref "B1") (pin "D9") (pinfunction "*D9_D9") (pintype "bidirectional"))
    )
    (net (code "70") (name "unconnected-(B1-*D10-PadD10)") (class "Default")
      (node (ref "B1") (pin "D10") (pinfunction "*D10_D10") (pintype "bidirectional"))
    )
    (net (code "71") (name "unconnected-(B1-*D11-PadD11)") (class "Default")
      (node (ref "B1") (pin "D11") (pinfunction "*D11_D11") (pintype "bidirectional"))
    )
    (net (code "72") (name "unconnected-(B1-PadA0)") (class "Default")
      (node (ref "B1") (pin "A0") (pinfunction "A0_A0") (pintype "bidirectional"))
    )
    (net (code "73") (name "unconnected-(B1-PadA1)") (class "Default")
      (node (ref "B1") (pin "A1") (pinfunction "A1_A1") (pintype "bidirectional"))
    )
    (net (code "74") (name "unconnected-(B1-PadA2)") (class "Default")
      (node (ref "B1") (pin "A2") (pinfunction "A2_A2") (pintype "bidirectional"))
    )
    (net (code "75") (name "unconnected-(B1-PadA3)") (class "Default")
      (node (ref "B1") (pin "A3") (pinfunction "A3_A3") (pintype "bidirectional"))
    )
    (net (code "76") (name "unconnected-(B1-PadA4)") (class "Default")
      (node (ref "B1") (pin "A4") (pinfunction "A4_A4") (pintype "bidirectional"))
    )
    (net (code "77") (name "unconnected-(B1-PadA5)") (class "Default")
      (node (ref "B1") (pin "A5") (pinfunction "A5_A5") (pintype "bidirectional"))
    )
    (net (code "78") (name "unconnected-(B1-PadAREF)") (class "Default")
      (node (ref "B1") (pin "AREF") (pinfunction "AREF_AREF") (pintype "bidirectional"))
    )
    (net (code "79") (name "unconnected-(B1-PadD2)") (class "Default")
      (node (ref "B1") (pin "D2") (pinfunction "D2_D2") (pintype "bidirectional"))
    )
    (net (code "80") (name "unconnected-(B1-PadD4)") (class "Default")
      (node (ref "B1") (pin "D4") (pinfunction "D4_D4") (pintype "bidirectional"))
    )
    (net (code "81") (name "unconnected-(B1-PadD7)") (class "Default")
      (node (ref "B1") (pin "D7") (pinfunction "D7_D7") (pintype "bidirectional"))
    )
    (net (code "82") (name "unconnected-(B1-PadD8)") (class "Default")
      (node (ref "B1") (pin "D8") (pinfunction "D8_D8") (pintype "bidirectional"))
    )
    (net (code "83") (name "unconnected-(B1-PadIOREF)") (class "Default")
      (node (ref "B1") (pin "IOREF") (pinfunction "IOREF_IOREF") (pintype "bidirectional"))
    )
    (net (code "84") (name "unconnected-(B1-PadRES)") (class "Default")
      (node (ref "B1") (pin "RES") (pinfunction "RES_RES") (pintype "bidirectional"))
    )
    (net (code "85") (name "unconnected-(J5-Pad7)") (class "Default")
      (node (ref "J5") (pin "7") (pinfunction "7_7") (pintype "passive"))
    )
    (net (code "86") (name "unconnected-(J6-Pad8)") (class "Default")
      (node (ref "J6") (pin "8") (pinfunction "8_8") (pintype "passive"))
    )
    (net (code "87") (name "unconnected-(U1-D1--Pad8)") (class "Default")
      (node (ref "U1") (pin "8") (pinfunction "D1-_8") (pintype "bidirectional"))
    )
    (net (code "88") (name "unconnected-(U3-IO1-Pad1)") (class "Default")
      (node (ref "U3") (pin "1") (pinfunction "IO1_1") (pintype "bidirectional"))
    )
    (net (code "89") (name "unconnected-(U3-IO2-Pad3)") (class "Default")
      (node (ref "U3") (pin "3") (pinfunction "IO2_3") (pintype "bidirectional"))
    )
    (net (code "90") (name "unconnected-(U4-CBUS0-Pad18)") (class "Default")
      (node (ref "U4") (pin "18") (pinfunction "CBUS0_18") (pintype "bidirectional"))
    )
    (net (code "91") (name "unconnected-(U4-CBUS1-Pad17)") (class "Default")
      (node (ref "U4") (pin "17") (pinfunction "CBUS1_17") (pintype "bidirectional"))
    )
    (net (code "92") (name "unconnected-(U4-CBUS2-Pad10)") (class "Default")
      (node (ref "U4") (pin "10") (pinfunction "CBUS2_10") (pintype "bidirectional"))
    )
    (net (code "93") (name "unconnected-(U4-CBUS3-Pad19)") (class "Default")
      (node (ref "U4") (pin "19") (pinfunction "CBUS3_19") (pintype "bidirectional"))
    )
    (net (code "94") (name "unconnected-(U4-~{DCD}-Pad8)") (class "Default")
      (node (ref "U4") (pin "8") (pinfunction "~{DCD}_8") (pintype "bidirectional"))
    )
    (net (code "95") (name "unconnected-(U4-~{DSR}-Pad7)") (class "Default")
      (node (ref "U4") (pin "7") (pinfunction "~{DSR}_7") (pintype "bidirectional"))
    )
    (net (code "96") (name "unconnected-(U4-~{RI}-Pad5)") (class "Default")
      (node (ref "U4") (pin "5") (pinfunction "~{RI}_5") (pintype "bidirectional"))
    )
    (net (code "97") (name "unconnected-(U5-IO1-Pad1)") (class "Default")
      (node (ref "U5") (pin "1") (pinfunction "IO1_1") (pintype "bidirectional"))
    )
    (net (code "98") (name "unconnected-(U5-IO2-Pad3)") (class "Default")
      (node (ref "U5") (pin "3") (pinfunction "IO2_3") (pintype "bidirectional"))
    )
  )
)
